# turntouch-remote-master.net
KiCad netlist of a schematic drawn in EAGLE
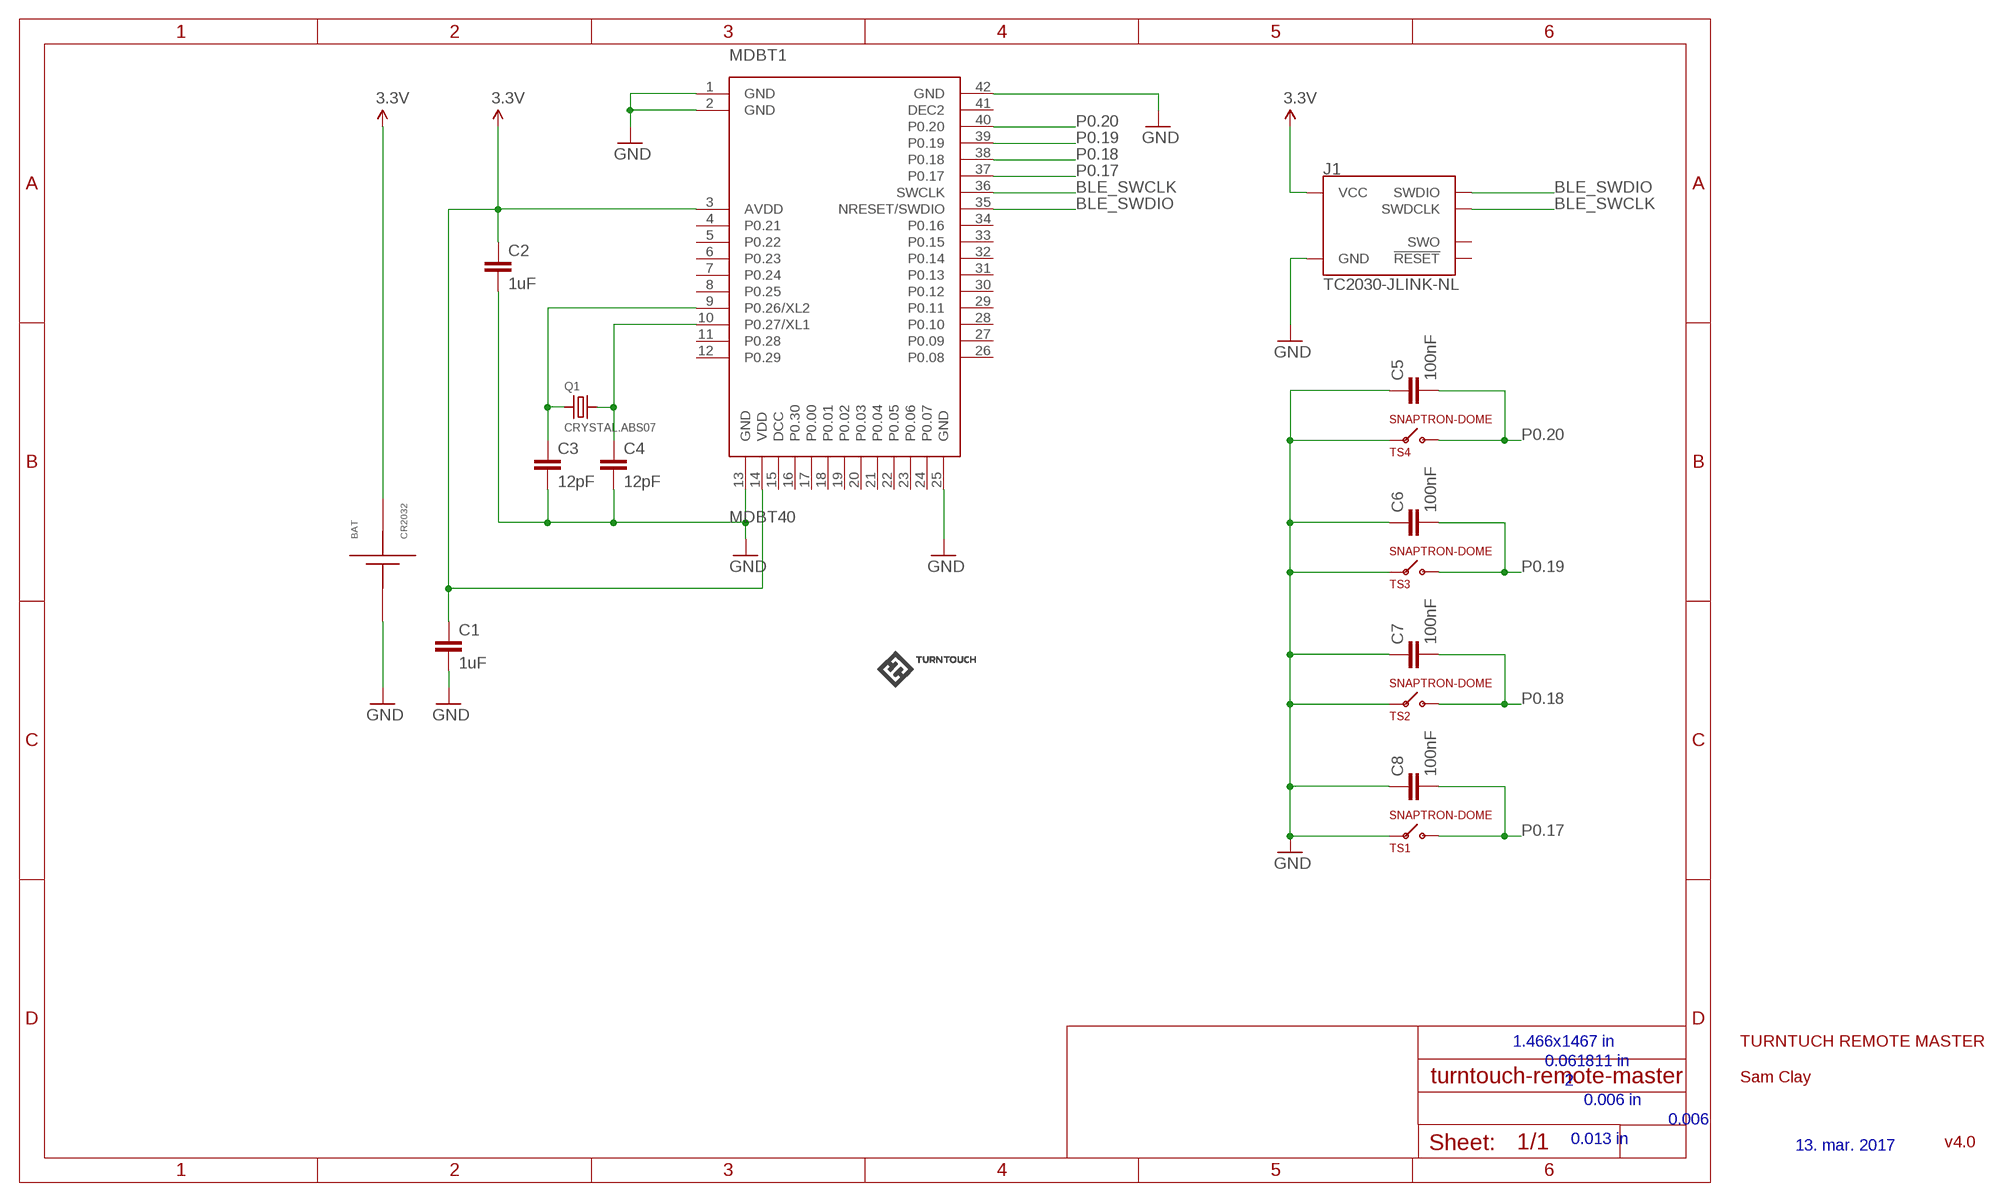
[diagram p0: schematic, sheet 1]

(export (version "E")
  (design (tool "Eeschema 10.0.6"))
  (components
    (comp (ref "BAT")
      (value "CR2032")
      (footprint "eagle-import:CR2032")
      (libsource (lib "eagle-import") (part "CR2032"))
    )
    (comp (ref "C1")
      (value "1uF")
      (footprint "eagle-import:0603-CAP")
      (libsource (lib "eagle-import") (part "0.1UF-25V(+80/-20%)(0603)"))
    )
    (comp (ref "C2")
      (value "1uF")
      (footprint "eagle-import:0603-CAP")
      (libsource (lib "eagle-import") (part "0.1UF-25V(+80/-20%)(0603)"))
    )
    (comp (ref "C3")
      (value "12pF")
      (footprint "eagle-import:0603-CAP")
      (libsource (lib "eagle-import") (part "0.1UF-25V(+80/-20%)(0603)"))
    )
    (comp (ref "C4")
      (value "12pF")
      (footprint "eagle-import:0603-CAP")
      (libsource (lib "eagle-import") (part "0.1UF-25V(+80/-20%)(0603)"))
    )
    (comp (ref "C5")
      (value "100nF")
      (footprint "eagle-import:0603-CAP")
      (libsource (lib "eagle-import") (part "0.1UF-25V(+80/-20%)(0603)"))
    )
    (comp (ref "C6")
      (value "100nF")
      (footprint "eagle-import:0603-CAP")
      (libsource (lib "eagle-import") (part "0.1UF-25V(+80/-20%)(0603)"))
    )
    (comp (ref "C7")
      (value "100nF")
      (footprint "eagle-import:0603-CAP")
      (libsource (lib "eagle-import") (part "0.1UF-25V(+80/-20%)(0603)"))
    )
    (comp (ref "C8")
      (value "100nF")
      (footprint "eagle-import:0603-CAP")
      (libsource (lib "eagle-import") (part "0.1UF-25V(+80/-20%)(0603)"))
    )
    (comp (ref "J1")
      (value "TC2030-JLINK-NL")
      (footprint "eagle-import:TC2030-IDC-NL")
      (libsource (lib "eagle-import") (part "TC2030-JLINK-NL"))
    )
    (comp (ref "LOGO")
      (value "TURNTOUCHLOGO200DPI")
      (footprint "eagle-import:LOGO")
      (libsource (lib "eagle-import") (part "TURNTOUCHLOGO200DPI"))
    )
    (comp (ref "MDBT1")
      (value "MDBT40")
      (footprint "eagle-import:MDBT40")
      (libsource (lib "eagle-import") (part "MDBT40"))
    )
    (comp (ref "Q1")
      (value "CRYSTAL.ABS07")
      (footprint "eagle-import:ABS07")
      (libsource (lib "eagle-import") (part "CRYSTAL.ABS07"))
    )
    (comp (ref "TS1")
      (value "SNAPTRON-DOME")
      (footprint "eagle-import:DOME-M-SERIES")
      (libsource (lib "eagle-import") (part "SNAPTRON-DOME"))
    )
    (comp (ref "TS2")
      (value "SNAPTRON-DOME")
      (footprint "eagle-import:DOME-M-SERIES")
      (libsource (lib "eagle-import") (part "SNAPTRON-DOME"))
    )
    (comp (ref "TS3")
      (value "SNAPTRON-DOME")
      (footprint "eagle-import:DOME-M-SERIES")
      (libsource (lib "eagle-import") (part "SNAPTRON-DOME"))
    )
    (comp (ref "TS4")
      (value "SNAPTRON-DOME")
      (footprint "eagle-import:DOME-M-SERIES")
      (libsource (lib "eagle-import") (part "SNAPTRON-DOME"))
    )
  )
  (nets
    (net (code "1") (name "/BLE_SWCLK") (class "Default")
      (node (ref "J1") (pin "4") (pinfunction "SWDCLK_4") (pintype "bidirectional"))
      (node (ref "MDBT1") (pin "36") (pinfunction "SWCLK_36") (pintype "bidirectional"))
    )
    (net (code "2") (name "/BLE_SWDIO") (class "Default")
      (node (ref "J1") (pin "2") (pinfunction "SWDIO_2") (pintype "bidirectional"))
      (node (ref "MDBT1") (pin "35") (pinfunction "NRESET/SWDIO_35") (pintype "bidirectional"))
    )
    (net (code "3") (name "/P0.17") (class "Default")
      (node (ref "C8") (pin "2") (pinfunction "2_2") (pintype "passive"))
      (node (ref "MDBT1") (pin "37") (pinfunction "P0.17_37") (pintype "bidirectional"))
      (node (ref "TS1") (pin "P$3") (pinfunction "B_P$3") (pintype "bidirectional"))
    )
    (net (code "4") (name "/P0.18") (class "Default")
      (node (ref "C7") (pin "2") (pinfunction "2_2") (pintype "passive"))
      (node (ref "MDBT1") (pin "38") (pinfunction "P0.18_38") (pintype "bidirectional"))
      (node (ref "TS2") (pin "P$3") (pinfunction "B_P$3") (pintype "bidirectional"))
    )
    (net (code "5") (name "/P0.19") (class "Default")
      (node (ref "C6") (pin "2") (pinfunction "2_2") (pintype "passive"))
      (node (ref "MDBT1") (pin "39") (pinfunction "P0.19_39") (pintype "bidirectional"))
      (node (ref "TS3") (pin "P$3") (pinfunction "B_P$3") (pintype "bidirectional"))
    )
    (net (code "6") (name "/P0.20") (class "Default")
      (node (ref "C5") (pin "2") (pinfunction "2_2") (pintype "passive"))
      (node (ref "MDBT1") (pin "40") (pinfunction "P0.20_40") (pintype "bidirectional"))
      (node (ref "TS4") (pin "P$3") (pinfunction "B_P$3") (pintype "bidirectional"))
    )
    (net (code "7") (name "3.3V") (class "Default")
      (node (ref "BAT") (pin "P$1") (pinfunction "VBAT_P$1") (pintype "bidirectional"))
      (node (ref "BAT") (pin "P$2") (pinfunction "VBAT_P$2") (pintype "bidirectional"))
      (node (ref "C1") (pin "1") (pinfunction "1_1") (pintype "passive"))
      (node (ref "C2") (pin "1") (pinfunction "1_1") (pintype "passive"))
      (node (ref "J1") (pin "1") (pinfunction "VCC_1") (pintype "bidirectional"))
      (node (ref "MDBT1") (pin "14") (pinfunction "VDD_14") (pintype "bidirectional"))
      (node (ref "MDBT1") (pin "3") (pinfunction "AVDD_3") (pintype "bidirectional"))
    )
    (net (code "8") (name "GND") (class "Default")
      (node (ref "BAT") (pin "GND") (pinfunction "GND_GND") (pintype "bidirectional"))
      (node (ref "C1") (pin "2") (pinfunction "2_2") (pintype "passive"))
      (node (ref "C2") (pin "2") (pinfunction "2_2") (pintype "passive"))
      (node (ref "C3") (pin "2") (pinfunction "2_2") (pintype "passive"))
      (node (ref "C4") (pin "2") (pinfunction "2_2") (pintype "passive"))
      (node (ref "C5") (pin "1") (pinfunction "1_1") (pintype "passive"))
      (node (ref "C6") (pin "1") (pinfunction "1_1") (pintype "passive"))
      (node (ref "C7") (pin "1") (pinfunction "1_1") (pintype "passive"))
      (node (ref "C8") (pin "1") (pinfunction "1_1") (pintype "passive"))
      (node (ref "J1") (pin "5") (pinfunction "GND_5") (pintype "bidirectional"))
      (node (ref "MDBT1") (pin "1") (pinfunction "GND_1") (pintype "bidirectional"))
      (node (ref "MDBT1") (pin "13") (pinfunction "GND_13") (pintype "bidirectional"))
      (node (ref "MDBT1") (pin "2") (pinfunction "GND_2") (pintype "bidirectional"))
      (node (ref "MDBT1") (pin "25") (pinfunction "GND_25") (pintype "bidirectional"))
      (node (ref "MDBT1") (pin "42") (pinfunction "GND_42") (pintype "bidirectional"))
      (node (ref "TS1") (pin "P$1") (pinfunction "V_P$1") (pintype "bidirectional"))
      (node (ref "TS1") (pin "P$2") (pinfunction "V_P$2") (pintype "bidirectional"))
      (node (ref "TS2") (pin "P$1") (pinfunction "V_P$1") (pintype "bidirectional"))
      (node (ref "TS2") (pin "P$2") (pinfunction "V_P$2") (pintype "bidirectional"))
      (node (ref "TS3") (pin "P$1") (pinfunction "V_P$1") (pintype "bidirectional"))
      (node (ref "TS3") (pin "P$2") (pinfunction "V_P$2") (pintype "bidirectional"))
      (node (ref "TS4") (pin "P$1") (pinfunction "V_P$1") (pintype "bidirectional"))
      (node (ref "TS4") (pin "P$2") (pinfunction "V_P$2") (pintype "bidirectional"))
    )
    (net (code "9") (name "Net-(MDBT1-P0.26{slash}XL2)") (class "Default")
      (node (ref "C3") (pin "1") (pinfunction "1_1") (pintype "passive"))
      (node (ref "MDBT1") (pin "9") (pinfunction "P0.26/XL2_9") (pintype "bidirectional"))
      (node (ref "Q1") (pin "1") (pinfunction "1_1") (pintype "passive"))
    )
    (net (code "10") (name "Net-(MDBT1-P0.27{slash}XL1)") (class "Default")
      (node (ref "C4") (pin "1") (pinfunction "1_1") (pintype "passive"))
      (node (ref "MDBT1") (pin "10") (pinfunction "P0.27/XL1_10") (pintype "bidirectional"))
      (node (ref "Q1") (pin "2") (pinfunction "2_2") (pintype "passive"))
    )
    (net (code "11") (name "unconnected-(J1-SWO-Pad6)") (class "Default")
      (node (ref "J1") (pin "6") (pinfunction "SWO_6") (pintype "bidirectional"))
    )
    (net (code "12") (name "unconnected-(J1-~{RESET}-Pad3)") (class "Default")
      (node (ref "J1") (pin "3") (pinfunction "~{RESET}_3") (pintype "bidirectional"))
    )
    (net (code "13") (name "unconnected-(MDBT1-DCC-Pad15)") (class "Default")
      (node (ref "MDBT1") (pin "15") (pinfunction "DCC_15") (pintype "bidirectional"))
    )
    (net (code "14") (name "unconnected-(MDBT1-DEC2-Pad41)") (class "Default")
      (node (ref "MDBT1") (pin "41") (pinfunction "DEC2_41") (pintype "bidirectional"))
    )
    (net (code "15") (name "unconnected-(MDBT1-P0.00-Pad17)") (class "Default")
      (node (ref "MDBT1") (pin "17") (pinfunction "P0.00_17") (pintype "bidirectional"))
    )
    (net (code "16") (name "unconnected-(MDBT1-P0.01-Pad18)") (class "Default")
      (node (ref "MDBT1") (pin "18") (pinfunction "P0.01_18") (pintype "bidirectional"))
    )
    (net (code "17") (name "unconnected-(MDBT1-P0.02-Pad19)") (class "Default")
      (node (ref "MDBT1") (pin "19") (pinfunction "P0.02_19") (pintype "bidirectional"))
    )
    (net (code "18") (name "unconnected-(MDBT1-P0.03-Pad20)") (class "Default")
      (node (ref "MDBT1") (pin "20") (pinfunction "P0.03_20") (pintype "bidirectional"))
    )
    (net (code "19") (name "unconnected-(MDBT1-P0.04-Pad21)") (class "Default")
      (node (ref "MDBT1") (pin "21") (pinfunction "P0.04_21") (pintype "bidirectional"))
    )
    (net (code "20") (name "unconnected-(MDBT1-P0.05-Pad22)") (class "Default")
      (node (ref "MDBT1") (pin "22") (pinfunction "P0.05_22") (pintype "bidirectional"))
    )
    (net (code "21") (name "unconnected-(MDBT1-P0.06-Pad23)") (class "Default")
      (node (ref "MDBT1") (pin "23") (pinfunction "P0.06_23") (pintype "bidirectional"))
    )
    (net (code "22") (name "unconnected-(MDBT1-P0.07-Pad24)") (class "Default")
      (node (ref "MDBT1") (pin "24") (pinfunction "P0.07_24") (pintype "bidirectional"))
    )
    (net (code "23") (name "unconnected-(MDBT1-P0.08-Pad26)") (class "Default")
      (node (ref "MDBT1") (pin "26") (pinfunction "P0.08_26") (pintype "bidirectional"))
    )
    (net (code "24") (name "unconnected-(MDBT1-P0.09-Pad27)") (class "Default")
      (node (ref "MDBT1") (pin "27") (pinfunction "P0.09_27") (pintype "bidirectional"))
    )
    (net (code "25") (name "unconnected-(MDBT1-P0.10-Pad28)") (class "Default")
      (node (ref "MDBT1") (pin "28") (pinfunction "P0.10_28") (pintype "bidirectional"))
    )
    (net (code "26") (name "unconnected-(MDBT1-P0.11-Pad29)") (class "Default")
      (node (ref "MDBT1") (pin "29") (pinfunction "P0.11_29") (pintype "bidirectional"))
    )
    (net (code "27") (name "unconnected-(MDBT1-P0.12-Pad30)") (class "Default")
      (node (ref "MDBT1") (pin "30") (pinfunction "P0.12_30") (pintype "bidirectional"))
    )
    (net (code "28") (name "unconnected-(MDBT1-P0.13-Pad31)") (class "Default")
      (node (ref "MDBT1") (pin "31") (pinfunction "P0.13_31") (pintype "bidirectional"))
    )
    (net (code "29") (name "unconnected-(MDBT1-P0.14-Pad32)") (class "Default")
      (node (ref "MDBT1") (pin "32") (pinfunction "P0.14_32") (pintype "bidirectional"))
    )
    (net (code "30") (name "unconnected-(MDBT1-P0.15-Pad33)") (class "Default")
      (node (ref "MDBT1") (pin "33") (pinfunction "P0.15_33") (pintype "bidirectional"))
    )
    (net (code "31") (name "unconnected-(MDBT1-P0.16-Pad34)") (class "Default")
      (node (ref "MDBT1") (pin "34") (pinfunction "P0.16_34") (pintype "bidirectional"))
    )
    (net (code "32") (name "unconnected-(MDBT1-P0.21-Pad4)") (class "Default")
      (node (ref "MDBT1") (pin "4") (pinfunction "P0.21_4") (pintype "bidirectional"))
    )
    (net (code "33") (name "unconnected-(MDBT1-P0.22-Pad5)") (class "Default")
      (node (ref "MDBT1") (pin "5") (pinfunction "P0.22_5") (pintype "bidirectional"))
    )
    (net (code "34") (name "unconnected-(MDBT1-P0.23-Pad6)") (class "Default")
      (node (ref "MDBT1") (pin "6") (pinfunction "P0.23_6") (pintype "bidirectional"))
    )
    (net (code "35") (name "unconnected-(MDBT1-P0.24-Pad7)") (class "Default")
      (node (ref "MDBT1") (pin "7") (pinfunction "P0.24_7") (pintype "bidirectional"))
    )
    (net (code "36") (name "unconnected-(MDBT1-P0.25-Pad8)") (class "Default")
      (node (ref "MDBT1") (pin "8") (pinfunction "P0.25_8") (pintype "bidirectional"))
    )
    (net (code "37") (name "unconnected-(MDBT1-P0.28-Pad11)") (class "Default")
      (node (ref "MDBT1") (pin "11") (pinfunction "P0.28_11") (pintype "bidirectional"))
    )
    (net (code "38") (name "unconnected-(MDBT1-P0.29-Pad12)") (class "Default")
      (node (ref "MDBT1") (pin "12") (pinfunction "P0.29_12") (pintype "bidirectional"))
    )
    (net (code "39") (name "unconnected-(MDBT1-P0.30-Pad16)") (class "Default")
      (node (ref "MDBT1") (pin "16") (pinfunction "P0.30_16") (pintype "bidirectional"))
    )
  )
)
